# main_board.net
KiCad netlist of a schematic drawn in EAGLE
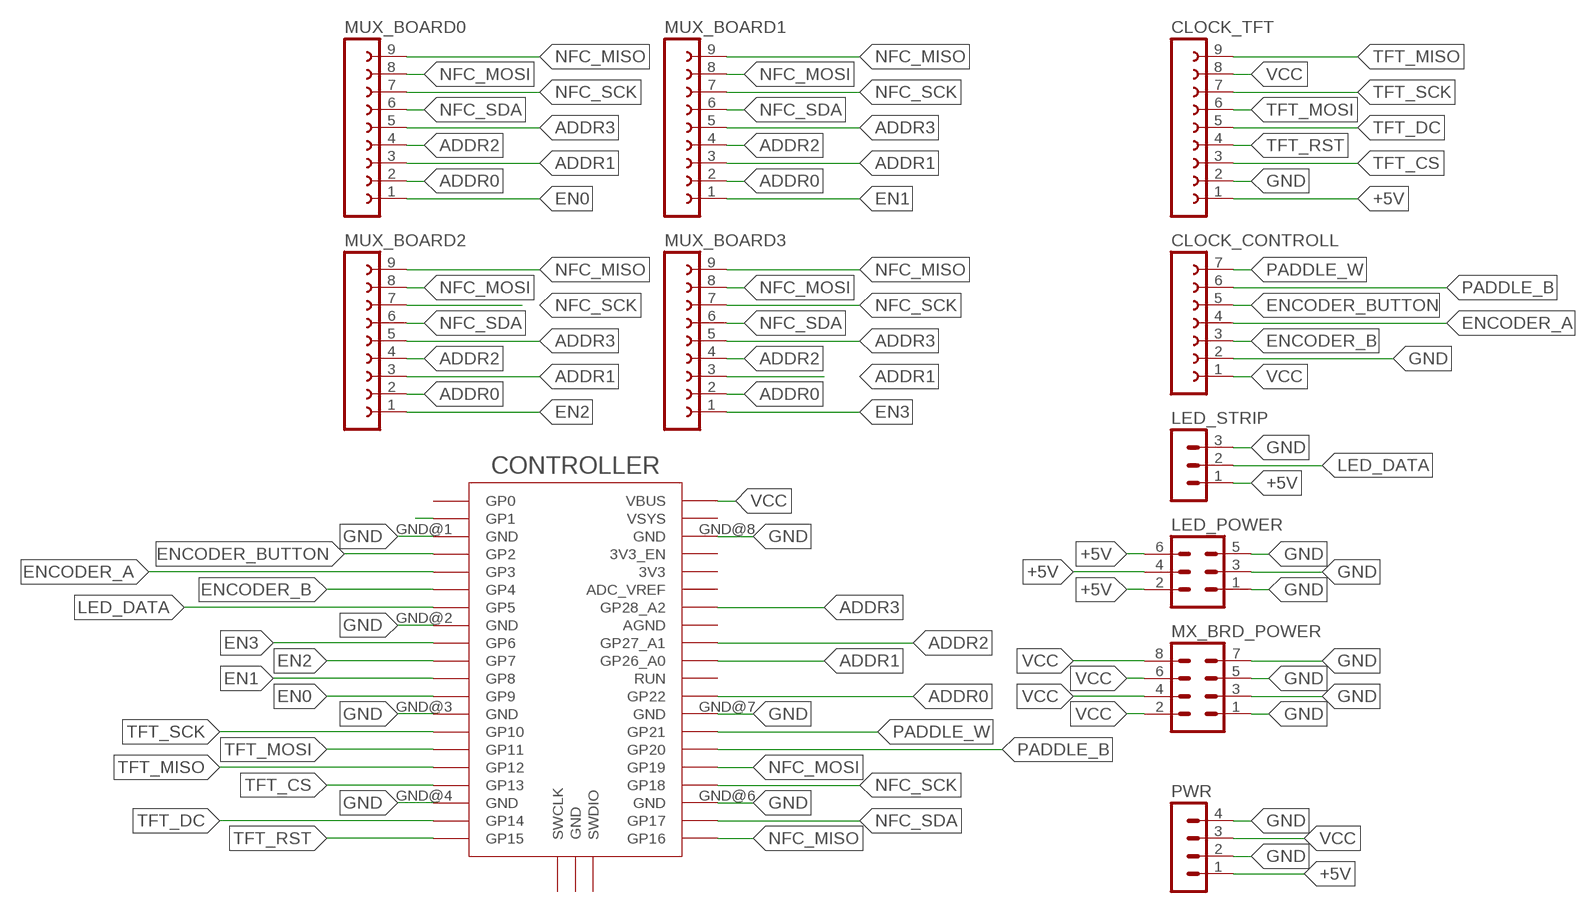
[diagram p0: schematic, sheet 1]

(export (version "E")
  (design (tool "Eeschema 10.0.6"))
  (components
    (comp (ref "CLOCK_CONTROLL")
      (value "FE07-1")
      (footprint "eagle-import:FE07")
      (libsource (lib "eagle-import") (part "FE07-1"))
    )
    (comp (ref "CLOCK_TFT")
      (value "FE09-1")
      (footprint "eagle-import:FE09")
      (libsource (lib "eagle-import") (part "FE09-1"))
    )
    (comp (ref "CONTROLLER")
      (value "RPI_PICO_IG-TH")
      (footprint "eagle-import:RPI_PICO_TH")
      (libsource (lib "eagle-import") (part "RPI_PICO_IG-TH"))
    )
    (comp (ref "LED_POWER")
      (value "MA03-2")
      (footprint "eagle-import:MA03-2")
      (libsource (lib "eagle-import") (part "MA03-2"))
    )
    (comp (ref "LED_STRIP")
      (value "MA03-1")
      (footprint "eagle-import:MA03-1")
      (libsource (lib "eagle-import") (part "MA03-1"))
    )
    (comp (ref "MUX_BOARD0")
      (value "FE09-1")
      (footprint "eagle-import:FE09")
      (libsource (lib "eagle-import") (part "FE09-1"))
    )
    (comp (ref "MUX_BOARD1")
      (value "FE09-1")
      (footprint "eagle-import:FE09")
      (libsource (lib "eagle-import") (part "FE09-1"))
    )
    (comp (ref "MUX_BOARD2")
      (value "FE09-1")
      (footprint "eagle-import:FE09")
      (libsource (lib "eagle-import") (part "FE09-1"))
    )
    (comp (ref "MUX_BOARD3")
      (value "FE09-1")
      (footprint "eagle-import:FE09")
      (libsource (lib "eagle-import") (part "FE09-1"))
    )
    (comp (ref "MX_BRD_POWER")
      (value "MA04-2")
      (footprint "eagle-import:MA04-2")
      (libsource (lib "eagle-import") (part "MA04-2"))
    )
    (comp (ref "PWR")
      (value "MA04-1")
      (footprint "eagle-import:MA04-1")
      (libsource (lib "eagle-import") (part "MA04-1"))
    )
  )
  (nets
    (net (code "1") (name "+5V") (class "Default")
      (node (ref "CLOCK_TFT") (pin "1") (pinfunction "1_1") (pintype "passive"))
      (node (ref "LED_POWER") (pin "2") (pinfunction "2_2") (pintype "passive"))
      (node (ref "LED_POWER") (pin "4") (pinfunction "4_4") (pintype "passive"))
      (node (ref "LED_POWER") (pin "6") (pinfunction "6_6") (pintype "passive"))
      (node (ref "LED_STRIP") (pin "1") (pinfunction "1_1") (pintype "passive"))
      (node (ref "PWR") (pin "1") (pinfunction "1_1") (pintype "passive"))
    )
    (net (code "2") (name "ADDR0") (class "Default")
      (node (ref "CONTROLLER") (pin "GP22") (pinfunction "GP22_GP22") (pintype "bidirectional"))
      (node (ref "MUX_BOARD0") (pin "2") (pinfunction "2_2") (pintype "passive"))
      (node (ref "MUX_BOARD1") (pin "2") (pinfunction "2_2") (pintype "passive"))
      (node (ref "MUX_BOARD2") (pin "2") (pinfunction "2_2") (pintype "passive"))
      (node (ref "MUX_BOARD3") (pin "2") (pinfunction "2_2") (pintype "passive"))
    )
    (net (code "3") (name "ADDR1") (class "Default")
      (node (ref "CONTROLLER") (pin "GP26_A0") (pinfunction "GP26_A0_GP26_A0") (pintype "bidirectional"))
      (node (ref "MUX_BOARD0") (pin "3") (pinfunction "3_3") (pintype "passive"))
      (node (ref "MUX_BOARD1") (pin "3") (pinfunction "3_3") (pintype "passive"))
      (node (ref "MUX_BOARD2") (pin "3") (pinfunction "3_3") (pintype "passive"))
      (node (ref "MUX_BOARD3") (pin "3") (pinfunction "3_3") (pintype "passive"))
    )
    (net (code "4") (name "ADDR2") (class "Default")
      (node (ref "CONTROLLER") (pin "GP27_A1") (pinfunction "GP27_A1_GP27_A1") (pintype "bidirectional"))
      (node (ref "MUX_BOARD0") (pin "4") (pinfunction "4_4") (pintype "passive"))
      (node (ref "MUX_BOARD1") (pin "4") (pinfunction "4_4") (pintype "passive"))
      (node (ref "MUX_BOARD2") (pin "4") (pinfunction "4_4") (pintype "passive"))
      (node (ref "MUX_BOARD3") (pin "4") (pinfunction "4_4") (pintype "passive"))
    )
    (net (code "5") (name "ADDR3") (class "Default")
      (node (ref "CONTROLLER") (pin "GP28_A2") (pinfunction "GP28_A2_GP28_A2") (pintype "bidirectional"))
      (node (ref "MUX_BOARD0") (pin "5") (pinfunction "5_5") (pintype "passive"))
      (node (ref "MUX_BOARD1") (pin "5") (pinfunction "5_5") (pintype "passive"))
      (node (ref "MUX_BOARD2") (pin "5") (pinfunction "5_5") (pintype "passive"))
      (node (ref "MUX_BOARD3") (pin "5") (pinfunction "5_5") (pintype "passive"))
    )
    (net (code "6") (name "EN0") (class "Default")
      (node (ref "CONTROLLER") (pin "GP9") (pinfunction "GP9_GP9") (pintype "bidirectional"))
      (node (ref "MUX_BOARD0") (pin "1") (pinfunction "1_1") (pintype "passive"))
    )
    (net (code "7") (name "EN1") (class "Default")
      (node (ref "CONTROLLER") (pin "GP8") (pinfunction "GP8_GP8") (pintype "bidirectional"))
      (node (ref "MUX_BOARD1") (pin "1") (pinfunction "1_1") (pintype "passive"))
    )
    (net (code "8") (name "EN2") (class "Default")
      (node (ref "CONTROLLER") (pin "GP7") (pinfunction "GP7_GP7") (pintype "bidirectional"))
      (node (ref "MUX_BOARD2") (pin "1") (pinfunction "1_1") (pintype "passive"))
    )
    (net (code "9") (name "EN3") (class "Default")
      (node (ref "CONTROLLER") (pin "GP6") (pinfunction "GP6_GP6") (pintype "bidirectional"))
      (node (ref "MUX_BOARD3") (pin "1") (pinfunction "1_1") (pintype "passive"))
    )
    (net (code "10") (name "ENCODER_A") (class "Default")
      (node (ref "CLOCK_CONTROLL") (pin "4") (pinfunction "4_4") (pintype "passive"))
      (node (ref "CONTROLLER") (pin "GP3") (pinfunction "GP3_GP3") (pintype "bidirectional"))
    )
    (net (code "11") (name "ENCODER_B") (class "Default")
      (node (ref "CLOCK_CONTROLL") (pin "3") (pinfunction "3_3") (pintype "passive"))
      (node (ref "CONTROLLER") (pin "GP4") (pinfunction "GP4_GP4") (pintype "bidirectional"))
    )
    (net (code "12") (name "ENCODER_BUTTON") (class "Default")
      (node (ref "CLOCK_CONTROLL") (pin "5") (pinfunction "5_5") (pintype "passive"))
      (node (ref "CONTROLLER") (pin "GP2") (pinfunction "GP2_GP2") (pintype "bidirectional"))
    )
    (net (code "13") (name "GND") (class "Default")
      (node (ref "CLOCK_CONTROLL") (pin "2") (pinfunction "2_2") (pintype "passive"))
      (node (ref "CLOCK_TFT") (pin "2") (pinfunction "2_2") (pintype "passive"))
      (node (ref "CONTROLLER") (pin "GND@1") (pinfunction "GND_GND@1") (pintype "bidirectional"))
      (node (ref "CONTROLLER") (pin "GND@2") (pinfunction "GND_GND@2") (pintype "bidirectional"))
      (node (ref "CONTROLLER") (pin "GND@3") (pinfunction "GND_GND@3") (pintype "bidirectional"))
      (node (ref "CONTROLLER") (pin "GND@4") (pinfunction "GND_GND@4") (pintype "bidirectional"))
      (node (ref "CONTROLLER") (pin "GND@6") (pinfunction "GND_GND@6") (pintype "bidirectional"))
      (node (ref "CONTROLLER") (pin "GND@7") (pinfunction "GND_GND@7") (pintype "bidirectional"))
      (node (ref "CONTROLLER") (pin "GND@8") (pinfunction "GND_GND@8") (pintype "bidirectional"))
      (node (ref "LED_POWER") (pin "1") (pinfunction "1_1") (pintype "passive"))
      (node (ref "LED_POWER") (pin "3") (pinfunction "3_3") (pintype "passive"))
      (node (ref "LED_POWER") (pin "5") (pinfunction "5_5") (pintype "passive"))
      (node (ref "LED_STRIP") (pin "3") (pinfunction "3_3") (pintype "passive"))
      (node (ref "MX_BRD_POWER") (pin "1") (pinfunction "1_1") (pintype "passive"))
      (node (ref "MX_BRD_POWER") (pin "3") (pinfunction "3_3") (pintype "passive"))
      (node (ref "MX_BRD_POWER") (pin "5") (pinfunction "5_5") (pintype "passive"))
      (node (ref "MX_BRD_POWER") (pin "7") (pinfunction "7_7") (pintype "passive"))
      (node (ref "PWR") (pin "2") (pinfunction "2_2") (pintype "passive"))
      (node (ref "PWR") (pin "4") (pinfunction "4_4") (pintype "passive"))
    )
    (net (code "14") (name "LED_DATA") (class "Default")
      (node (ref "CONTROLLER") (pin "GP5") (pinfunction "GP5_GP5") (pintype "bidirectional"))
      (node (ref "LED_STRIP") (pin "2") (pinfunction "2_2") (pintype "passive"))
    )
    (net (code "15") (name "NFC_MISO") (class "Default")
      (node (ref "CONTROLLER") (pin "GP16") (pinfunction "GP16_GP16") (pintype "bidirectional"))
      (node (ref "MUX_BOARD0") (pin "9") (pinfunction "9_9") (pintype "passive"))
      (node (ref "MUX_BOARD1") (pin "9") (pinfunction "9_9") (pintype "passive"))
      (node (ref "MUX_BOARD2") (pin "9") (pinfunction "9_9") (pintype "passive"))
      (node (ref "MUX_BOARD3") (pin "9") (pinfunction "9_9") (pintype "passive"))
    )
    (net (code "16") (name "NFC_MOSI") (class "Default")
      (node (ref "CONTROLLER") (pin "GP19") (pinfunction "GP19_GP19") (pintype "bidirectional"))
      (node (ref "MUX_BOARD0") (pin "8") (pinfunction "8_8") (pintype "passive"))
      (node (ref "MUX_BOARD1") (pin "8") (pinfunction "8_8") (pintype "passive"))
      (node (ref "MUX_BOARD2") (pin "8") (pinfunction "8_8") (pintype "passive"))
      (node (ref "MUX_BOARD3") (pin "8") (pinfunction "8_8") (pintype "passive"))
    )
    (net (code "17") (name "NFC_SCK") (class "Default")
      (node (ref "CONTROLLER") (pin "GP18") (pinfunction "GP18_GP18") (pintype "bidirectional"))
      (node (ref "MUX_BOARD0") (pin "7") (pinfunction "7_7") (pintype "passive"))
      (node (ref "MUX_BOARD1") (pin "7") (pinfunction "7_7") (pintype "passive"))
      (node (ref "MUX_BOARD2") (pin "7") (pinfunction "7_7") (pintype "passive"))
      (node (ref "MUX_BOARD3") (pin "7") (pinfunction "7_7") (pintype "passive"))
    )
    (net (code "18") (name "NFC_SDA") (class "Default")
      (node (ref "CONTROLLER") (pin "GP17") (pinfunction "GP17_GP17") (pintype "bidirectional"))
      (node (ref "MUX_BOARD0") (pin "6") (pinfunction "6_6") (pintype "passive"))
      (node (ref "MUX_BOARD1") (pin "6") (pinfunction "6_6") (pintype "passive"))
      (node (ref "MUX_BOARD2") (pin "6") (pinfunction "6_6") (pintype "passive"))
      (node (ref "MUX_BOARD3") (pin "6") (pinfunction "6_6") (pintype "passive"))
    )
    (net (code "19") (name "PADDLE_B") (class "Default")
      (node (ref "CLOCK_CONTROLL") (pin "6") (pinfunction "6_6") (pintype "passive"))
      (node (ref "CONTROLLER") (pin "GP20") (pinfunction "GP20_GP20") (pintype "bidirectional"))
    )
    (net (code "20") (name "PADDLE_W") (class "Default")
      (node (ref "CLOCK_CONTROLL") (pin "7") (pinfunction "7_7") (pintype "passive"))
      (node (ref "CONTROLLER") (pin "GP21") (pinfunction "GP21_GP21") (pintype "bidirectional"))
    )
    (net (code "21") (name "TFT_CS") (class "Default")
      (node (ref "CLOCK_TFT") (pin "3") (pinfunction "3_3") (pintype "passive"))
      (node (ref "CONTROLLER") (pin "GP13") (pinfunction "GP13_GP13") (pintype "bidirectional"))
    )
    (net (code "22") (name "TFT_DC") (class "Default")
      (node (ref "CLOCK_TFT") (pin "5") (pinfunction "5_5") (pintype "passive"))
      (node (ref "CONTROLLER") (pin "GP14") (pinfunction "GP14_GP14") (pintype "bidirectional"))
    )
    (net (code "23") (name "TFT_MISO") (class "Default")
      (node (ref "CLOCK_TFT") (pin "9") (pinfunction "9_9") (pintype "passive"))
      (node (ref "CONTROLLER") (pin "GP12") (pinfunction "GP12_GP12") (pintype "bidirectional"))
    )
    (net (code "24") (name "TFT_MOSI") (class "Default")
      (node (ref "CLOCK_TFT") (pin "6") (pinfunction "6_6") (pintype "passive"))
      (node (ref "CONTROLLER") (pin "GP11") (pinfunction "GP11_GP11") (pintype "bidirectional"))
    )
    (net (code "25") (name "TFT_RST") (class "Default")
      (node (ref "CLOCK_TFT") (pin "4") (pinfunction "4_4") (pintype "passive"))
      (node (ref "CONTROLLER") (pin "GP15") (pinfunction "GP15_GP15") (pintype "bidirectional"))
    )
    (net (code "26") (name "TFT_SCK") (class "Default")
      (node (ref "CLOCK_TFT") (pin "7") (pinfunction "7_7") (pintype "passive"))
      (node (ref "CONTROLLER") (pin "GP10") (pinfunction "GP10_GP10") (pintype "bidirectional"))
    )
    (net (code "27") (name "VCC") (class "Default")
      (node (ref "CLOCK_CONTROLL") (pin "1") (pinfunction "1_1") (pintype "passive"))
      (node (ref "CLOCK_TFT") (pin "8") (pinfunction "8_8") (pintype "passive"))
      (node (ref "CONTROLLER") (pin "VBUS") (pinfunction "VBUS_VBUS") (pintype "bidirectional"))
      (node (ref "MX_BRD_POWER") (pin "2") (pinfunction "2_2") (pintype "passive"))
      (node (ref "MX_BRD_POWER") (pin "4") (pinfunction "4_4") (pintype "passive"))
      (node (ref "MX_BRD_POWER") (pin "6") (pinfunction "6_6") (pintype "passive"))
      (node (ref "MX_BRD_POWER") (pin "8") (pinfunction "8_8") (pintype "passive"))
      (node (ref "PWR") (pin "3") (pinfunction "3_3") (pintype "passive"))
    )
    (net (code "28") (name "unconnected-(CONTROLLER-GND-PadGND@5)") (class "Default")
      (node (ref "CONTROLLER") (pin "GND@5") (pinfunction "GND_GND@5") (pintype "bidirectional"))
    )
    (net (code "29") (name "unconnected-(CONTROLLER-Pad3V3)") (class "Default")
      (node (ref "CONTROLLER") (pin "3V3") (pinfunction "3V3_3V3") (pintype "bidirectional"))
    )
    (net (code "30") (name "unconnected-(CONTROLLER-Pad3V3_EN)") (class "Default")
      (node (ref "CONTROLLER") (pin "3V3_EN") (pinfunction "3V3_EN_3V3_EN") (pintype "bidirectional"))
    )
    (net (code "31") (name "unconnected-(CONTROLLER-PadADC_VREF)") (class "Default")
      (node (ref "CONTROLLER") (pin "ADC_VREF") (pinfunction "ADC_VREF_ADC_VREF") (pintype "bidirectional"))
    )
    (net (code "32") (name "unconnected-(CONTROLLER-PadAGND)") (class "Default")
      (node (ref "CONTROLLER") (pin "AGND") (pinfunction "AGND_AGND") (pintype "bidirectional"))
    )
    (net (code "33") (name "unconnected-(CONTROLLER-PadGP0)") (class "Default")
      (node (ref "CONTROLLER") (pin "GP0") (pinfunction "GP0_GP0") (pintype "bidirectional"))
    )
    (net (code "34") (name "unconnected-(CONTROLLER-PadGP1)") (class "Default")
      (node (ref "CONTROLLER") (pin "GP1") (pinfunction "GP1_GP1") (pintype "bidirectional"))
    )
    (net (code "35") (name "unconnected-(CONTROLLER-PadRUN)") (class "Default")
      (node (ref "CONTROLLER") (pin "RUN") (pinfunction "RUN_RUN") (pintype "bidirectional"))
    )
    (net (code "36") (name "unconnected-(CONTROLLER-PadSWCLK)") (class "Default")
      (node (ref "CONTROLLER") (pin "SWCLK") (pinfunction "SWCLK_SWCLK") (pintype "bidirectional"))
    )
    (net (code "37") (name "unconnected-(CONTROLLER-PadSWDIO)") (class "Default")
      (node (ref "CONTROLLER") (pin "SWDIO") (pinfunction "SWDIO_SWDIO") (pintype "bidirectional"))
    )
    (net (code "38") (name "unconnected-(CONTROLLER-PadVSYS)") (class "Default")
      (node (ref "CONTROLLER") (pin "VSYS") (pinfunction "VSYS_VSYS") (pintype "bidirectional"))
    )
  )
)
